# Level_Sensor_v1.net
KiCad netlist of a schematic drawn in EAGLE
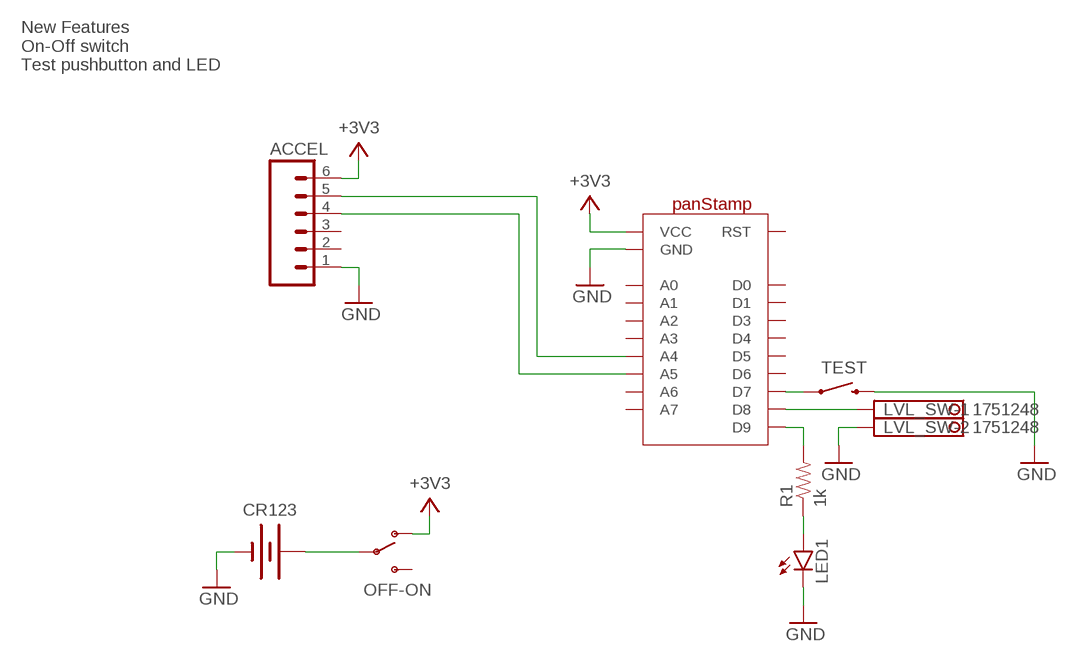
[diagram p0: schematic, sheet 1]

(export (version "E")
  (design (tool "Eeschema 10.0.6"))
  (components
    (comp (ref "ACCEL")
      (value "M06LONGPADS")
      (footprint "eagle-import:1X06_LONGPADS")
      (libsource (lib "eagle-import") (part "M06LONGPADS"))
    )
    (comp (ref "CR123")
      (value "BATTERY_CR123_SINGLE")
      (footprint "eagle-import:BATTERY_CR123")
      (libsource (lib "eagle-import") (part "BATTERY_CR123_SINGLE"))
    )
    (comp (ref "LED1")
      (value "LED3MM")
      (footprint "eagle-import:LED3MM")
      (libsource (lib "eagle-import") (part "LED3MM"))
    )
    (comp (ref "LVL_SW")
      (value "1751248")
      (footprint "eagle-import:1751248")
      (libsource (lib "eagle-import") (part "1751248"))
    )
    (comp (ref "OFF-ON")
      (value "SWITCH-SPDTPTH")
      (footprint "eagle-import:SWITCH-SPDT")
      (libsource (lib "eagle-import") (part "SWITCH-SPDTPTH"))
    )
    (comp (ref "R1")
      (value "1k")
      (footprint "eagle-import:AXIAL-0.4")
      (libsource (lib "eagle-import") (part "RESISTORPTH-1/4W"))
    )
    (comp (ref "TEST")
      (value "SWITCH-MOMENTARY-2PTH")
      (footprint "eagle-import:TACTILE-PTH")
      (libsource (lib "eagle-import") (part "SWITCH-MOMENTARY-2PTH"))
    )
    (comp (ref "U$1")
      (value "PANSTAMPWITH_TEXT")
      (footprint "eagle-import:PANSTAMP")
      (libsource (lib "eagle-import") (part "PANSTAMPWITH_TEXT"))
    )
  )
  (nets
    (net (code "1") (name "+3V3") (class "Default")
      (node (ref "ACCEL") (pin "6") (pinfunction "6_6") (pintype "passive"))
      (node (ref "OFF-ON") (pin "1") (pinfunction "O_1") (pintype "passive"))
      (node (ref "U$1") (pin "VCC") (pinfunction "VCC_VCC") (pintype "power_in"))
    )
    (net (code "2") (name "GND") (class "Default")
      (node (ref "ACCEL") (pin "1") (pinfunction "1_1") (pintype "passive"))
      (node (ref "CR123") (pin "NEG") (pinfunction "-_NEG") (pintype "power_in"))
      (node (ref "LED1") (pin "K") (pinfunction "C_K") (pintype "passive"))
      (node (ref "LVL_SW") (pin "2") (pinfunction "K_2") (pintype "passive"))
      (node (ref "TEST") (pin "3") (pinfunction "2_3") (pintype "passive"))
      (node (ref "U$1") (pin "GND$1") (pinfunction "GND_GND$1") (pintype "power_in"))
      (node (ref "U$1") (pin "GND$15") (pinfunction "GND_GND$15") (pintype "power_in"))
      (node (ref "U$1") (pin "GND$23") (pinfunction "GND_GND$23") (pintype "power_in"))
      (node (ref "U$1") (pin "GND$24") (pinfunction "GND_GND$24") (pintype "power_in"))
      (node (ref "U$1") (pin "GND$7") (pinfunction "GND_GND$7") (pintype "power_in"))
    )
    (net (code "3") (name "Net-(ACCEL-Pad4)") (class "Default")
      (node (ref "ACCEL") (pin "4") (pinfunction "4_4") (pintype "passive"))
      (node (ref "U$1") (pin "A5") (pinfunction "A5_A5") (pintype "bidirectional"))
    )
    (net (code "4") (name "Net-(ACCEL-Pad5)") (class "Default")
      (node (ref "ACCEL") (pin "5") (pinfunction "5_5") (pintype "passive"))
      (node (ref "U$1") (pin "A4") (pinfunction "A4_A4") (pintype "bidirectional"))
    )
    (net (code "5") (name "Net-(CR123-+)") (class "Default")
      (node (ref "CR123") (pin "POS") (pinfunction "+_POS") (pintype "power_in"))
      (node (ref "OFF-ON") (pin "2") (pinfunction "P_2") (pintype "passive"))
    )
    (net (code "6") (name "Net-(LVL_SWA-K)") (class "Default")
      (node (ref "LVL_SW") (pin "1") (pinfunction "K_1") (pintype "passive"))
      (node (ref "U$1") (pin "D8") (pinfunction "D8_D8") (pintype "bidirectional"))
    )
    (net (code "7") (name "Net-(R1-1)") (class "Default")
      (node (ref "LED1") (pin "A") (pinfunction "A_A") (pintype "passive"))
      (node (ref "R1") (pin "P$1") (pinfunction "1_P$1") (pintype "passive"))
    )
    (net (code "8") (name "Net-(R1-2)") (class "Default")
      (node (ref "R1") (pin "P$2") (pinfunction "2_P$2") (pintype "passive"))
      (node (ref "U$1") (pin "D9") (pinfunction "D9_D9") (pintype "bidirectional"))
    )
    (net (code "9") (name "Net-(TEST-Pad1)") (class "Default")
      (node (ref "TEST") (pin "1") (pinfunction "1_1") (pintype "passive"))
      (node (ref "U$1") (pin "D7") (pinfunction "D7_D7") (pintype "bidirectional"))
    )
    (net (code "10") (name "unconnected-(ACCEL-Pad2)") (class "Default")
      (node (ref "ACCEL") (pin "2") (pinfunction "2_2") (pintype "passive"))
    )
    (net (code "11") (name "unconnected-(ACCEL-Pad3)") (class "Default")
      (node (ref "ACCEL") (pin "3") (pinfunction "3_3") (pintype "passive"))
    )
    (net (code "12") (name "unconnected-(OFF-ON-S-Pad3)") (class "Default")
      (node (ref "OFF-ON") (pin "3") (pinfunction "S_3") (pintype "passive"))
    )
    (net (code "13") (name "unconnected-(U$1-PadA0)") (class "Default")
      (node (ref "U$1") (pin "A0") (pinfunction "A0_A0") (pintype "bidirectional"))
    )
    (net (code "14") (name "unconnected-(U$1-PadA1)") (class "Default")
      (node (ref "U$1") (pin "A1") (pinfunction "A1_A1") (pintype "bidirectional"))
    )
    (net (code "15") (name "unconnected-(U$1-PadA2)") (class "Default")
      (node (ref "U$1") (pin "A2") (pinfunction "A2_A2") (pintype "bidirectional"))
    )
    (net (code "16") (name "unconnected-(U$1-PadA3)") (class "Default")
      (node (ref "U$1") (pin "A3") (pinfunction "A3_A3") (pintype "bidirectional"))
    )
    (net (code "17") (name "unconnected-(U$1-PadA6)") (class "Default")
      (node (ref "U$1") (pin "A6") (pinfunction "A6_A6") (pintype "bidirectional"))
    )
    (net (code "18") (name "unconnected-(U$1-PadA7)") (class "Default")
      (node (ref "U$1") (pin "A7") (pinfunction "A7_A7") (pintype "bidirectional"))
    )
    (net (code "19") (name "unconnected-(U$1-PadD0)") (class "Default")
      (node (ref "U$1") (pin "D0") (pinfunction "D0_D0") (pintype "bidirectional"))
    )
    (net (code "20") (name "unconnected-(U$1-PadD1)") (class "Default")
      (node (ref "U$1") (pin "D1") (pinfunction "D1_D1") (pintype "bidirectional"))
    )
    (net (code "21") (name "unconnected-(U$1-PadD3)") (class "Default")
      (node (ref "U$1") (pin "D3") (pinfunction "D3_D3") (pintype "bidirectional"))
    )
    (net (code "22") (name "unconnected-(U$1-PadD4)") (class "Default")
      (node (ref "U$1") (pin "D4") (pinfunction "D4_D4") (pintype "bidirectional"))
    )
    (net (code "23") (name "unconnected-(U$1-PadD5)") (class "Default")
      (node (ref "U$1") (pin "D5") (pinfunction "D5_D5") (pintype "bidirectional"))
    )
    (net (code "24") (name "unconnected-(U$1-PadD6)") (class "Default")
      (node (ref "U$1") (pin "D6") (pinfunction "D6_D6") (pintype "bidirectional"))
    )
    (net (code "25") (name "unconnected-(U$1-RST-PadRESET)") (class "Default")
      (node (ref "U$1") (pin "RESET") (pinfunction "RST_RESET") (pintype "bidirectional"))
    )
  )
)
